# 1_Power.net
KiCad netlist of a schematic drawn in Altium Designer
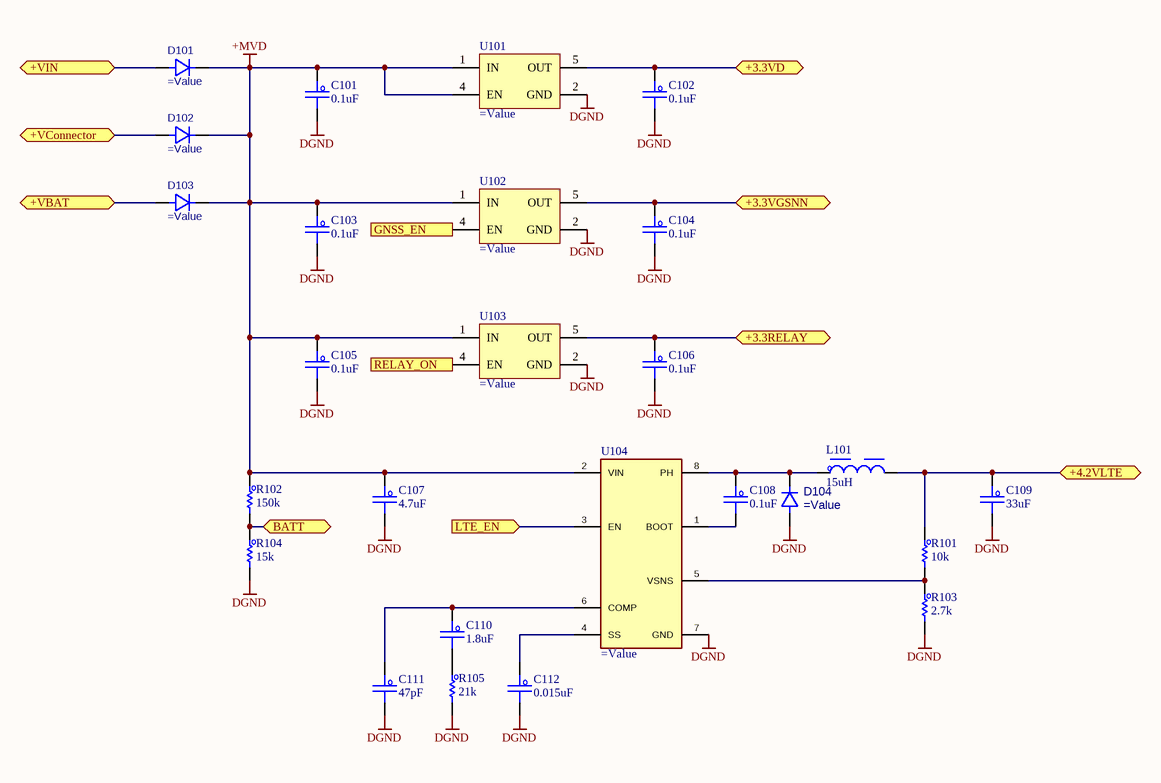
[diagram p0: 1_Power.SchDoc]

(export (version "E")
  (design (tool "Eeschema 10.0.6"))
  (components
    (comp (ref "C101")
      (value "0.1uF")
      (footprint "C_0603")
      (description "CAP CER 0.1UF 50V X7R 0603")
      (fields (field (name "MANUFACTURER") "KEMET") (field (name "PARTNUMBER") "C0603C104K5RACTU"))
      (libsource (lib "UUSymbol") (part "C_Capacitor"))
    )
    (comp (ref "C102")
      (value "0.1uF")
      (footprint "C_0603")
      (description "CAP CER 0.1UF 50V X7R 0603")
      (fields (field (name "MANUFACTURER") "KEMET") (field (name "PARTNUMBER") "C0603C104K5RACTU"))
      (libsource (lib "UUSymbol") (part "C_Capacitor"))
    )
    (comp (ref "C103")
      (value "0.1uF")
      (footprint "C_0603")
      (description "CAP CER 0.1UF 50V X7R 0603")
      (fields (field (name "MANUFACTURER") "KEMET") (field (name "PARTNUMBER") "C0603C104K5RACTU"))
      (libsource (lib "UUSymbol") (part "C_Capacitor"))
    )
    (comp (ref "C104")
      (value "0.1uF")
      (footprint "C_0603")
      (description "CAP CER 0.1UF 50V X7R 0603")
      (fields (field (name "MANUFACTURER") "KEMET") (field (name "PARTNUMBER") "C0603C104K5RACTU"))
      (libsource (lib "UUSymbol") (part "C_Capacitor"))
    )
    (comp (ref "C105")
      (value "0.1uF")
      (footprint "C_0603")
      (description "CAP CER 0.1UF 50V X7R 0603")
      (fields (field (name "MANUFACTURER") "KEMET") (field (name "PARTNUMBER") "C0603C104K5RACTU"))
      (libsource (lib "UUSymbol") (part "C_Capacitor"))
    )
    (comp (ref "C106")
      (value "0.1uF")
      (footprint "C_0603")
      (description "CAP CER 0.1UF 50V X7R 0603")
      (fields (field (name "MANUFACTURER") "KEMET") (field (name "PARTNUMBER") "C0603C104K5RACTU"))
      (libsource (lib "UUSymbol") (part "C_Capacitor"))
    )
    (comp (ref "C107")
      (value "4.7uF")
      (footprint "C_1206")
      (description "CAP CER 4.7UF 50V X7R 1206")
      (fields (field (name "MANUFACTURER") "KEMET") (field (name "PARTNUMBER") "C1206C475K5RAC7800"))
      (libsource (lib "UUSymbol") (part "C_Capacitor"))
    )
    (comp (ref "C108")
      (value "0.1uF")
      (footprint "C_0603")
      (description "CAP CER 0.1UF 50V X7R 0603")
      (fields (field (name "MANUFACTURER") "KEMET") (field (name "PARTNUMBER") "C0603C104K5RACTU"))
      (libsource (lib "UUSymbol") (part "C_Capacitor"))
    )
    (comp (ref "C109")
      (value "33uF")
      (footprint "C_0805")
      (description "CAP CER 33UF 10V X5R 0805")
      (fields
        (field (name "MANUFACTURER") "TDK Corporation")
        (field (name "PARTNUMBER") "C2012X5R1A336M125AC")
      )
      (libsource (lib "UUSymbol") (part "C_Capacitor"))
    )
    (comp (ref "C110")
      (value "1.8uF")
      (footprint "C_0603")
      (description "CAP CER 1800PF 50V X7R 0603")
      (fields (field (name "MANUFACTURER") "KEMET") (field (name "PARTNUMBER") "C0603C182K5RAC7867"))
      (libsource (lib "UUSymbol") (part "C_Capacitor"))
    )
    (comp (ref "C111")
      (value "47pF")
      (footprint "C_0603")
      (description "CAP CER 47PF 50V X7R 0603")
      (fields (field (name "MANUFACTURER") "KEMET") (field (name "PARTNUMBER") "C0603C470J5RAC7867"))
      (libsource (lib "UUSymbol") (part "C_Capacitor"))
    )
    (comp (ref "C112")
      (value "0.015uF")
      (footprint "C_0603")
      (description "CAP CER 15PF 50V C0G/NP0 0603")
      (fields (field (name "MANUFACTURER") "KEMET") (field (name "PARTNUMBER") "C0603C150J5GAC7867"))
      (libsource (lib "UUSymbol") (part "C_Capacitor"))
    )
    (comp (ref "D101")
      (value "~")
      (footprint "SOD323")
      (description "DIODE SCHOTTKY 40V 2A 0603")
      (fields (field (name "MANUFACTURER") "Slkor(SLKORMICRO Elec.)") (field (name "PARTNUMBER") "SD103AWS"))
      (libsource (lib "UUSymbol") (part "D_PW_SD103AWS"))
    )
    (comp (ref "D102")
      (value "~")
      (footprint "SOD323")
      (description "DIODE SCHOTTKY 40V 2A 0603")
      (fields (field (name "MANUFACTURER") "Slkor(SLKORMICRO Elec.)") (field (name "PARTNUMBER") "SD103AWS"))
      (libsource (lib "UUSymbol") (part "D_PW_SD103AWS"))
    )
    (comp (ref "D103")
      (value "~")
      (footprint "SOD323")
      (description "DIODE SCHOTTKY 40V 2A 0603")
      (fields (field (name "MANUFACTURER") "Slkor(SLKORMICRO Elec.)") (field (name "PARTNUMBER") "SD103AWS"))
      (libsource (lib "UUSymbol") (part "D_PW_SD103AWS"))
    )
    (comp (ref "D104")
      (value "~")
      (footprint "DFN119P160X30-2M")
      (description "DIODE SCHOTTKY 30V 2A 0603")
      (fields
        (field (name "MANUFACTURER") "Vishay General Semiconductor - Diodes Division")
        (field (name "PARTNUMBER") "VSKY20301608-G4-08")
      )
      (libsource (lib "UUSymbol") (part "D_PW_VSKY20301608"))
    )
    (comp (ref "L101")
      (value "15uH")
      (footprint "IND_04054150_WRE")
      (description "FIXED IND 15UH 2A 86 MOHM SMD")
      (fields (field (name "MANUFACTURER") "Würth Elektronik") (field (name "PARTNUMBER") "74404054150"))
      (libsource (lib "UUSymbol") (part "L_74404054150"))
    )
    (comp (ref "R101")
      (value "10k")
      (footprint "R_0603")
      (description "RES 10K OHM 5% 1/10W 0603")
      (fields (field (name "MANUFACTURER") "Vishay Dale") (field (name "PARTNUMBER") "CRCW060310K0JNEBC"))
      (libsource (lib "UUSymbol") (part "R_Resister"))
    )
    (comp (ref "R102")
      (value "150k")
      (footprint "R_0603")
      (description "RES SMD 150K OHM 1% 1/10W 0603")
      (fields (field (name "MANUFACTURER") "Vishay Dale") (field (name "PARTNUMBER") "CRCW0603150KFKEAC"))
      (libsource (lib "UUSymbol") (part "R_Resister"))
    )
    (comp (ref "R103")
      (value "2.7k")
      (footprint "R_0603")
      (description "RES 2.7K OHM 5% 1/10W 0603")
      (fields (field (name "MANUFACTURER") "Vishay Dale") (field (name "PARTNUMBER") "CRCW06032K70JNEAC"))
      (libsource (lib "UUSymbol") (part "R_Resister"))
    )
    (comp (ref "R104")
      (value "15k")
      (footprint "R_0603")
      (description "RES 15K OHM 5% 1/10W 0603")
      (fields (field (name "MANUFACTURER") "Vishay Dale") (field (name "PARTNUMBER") "CRCW060315K0JNEAC"))
      (libsource (lib "UUSymbol") (part "R_Resister"))
    )
    (comp (ref "R105")
      (value "21k")
      (footprint "R_0603")
      (description "RES SMD 150K OHM 1% 1/10W 0603")
      (libsource (lib "UUSymbol") (part "R_Resister"))
    )
    (comp (ref "U101")
      (value "~")
      (footprint "SOT95P280X145-5N")
      (description "200mA 360mV@(10mA) Fixed 3.3V~3.3V Positive 1 36V SOT-23-5 Linear Voltage Regulators (LDO) ROHS")
      (fields (field (name "PARTNUMBER") "RT9069-33GB") (field (name "MANUFACTURER") "Richtek Tech"))
      (libsource (lib "UUSymbol") (part "IC_LDO_RT9069-33GB"))
    )
    (comp (ref "U102")
      (value "~")
      (footprint "SOT95P280X145-5N")
      (description "200mA 360mV@(10mA) Fixed 3.3V~3.3V Positive 1 36V SOT-23-5 Linear Voltage Regulators (LDO) ROHS")
      (fields (field (name "PARTNUMBER") "RT9069-33GB") (field (name "MANUFACTURER") "Richtek Tech"))
      (libsource (lib "UUSymbol") (part "IC_LDO_RT9069-33GB"))
    )
    (comp (ref "U103")
      (value "~")
      (footprint "SOT95P280X145-5N")
      (description "200mA 360mV@(10mA) Fixed 3.3V~3.3V Positive 1 36V SOT-23-5 Linear Voltage Regulators (LDO) ROHS")
      (fields (field (name "PARTNUMBER") "RT9069-33GB") (field (name "MANUFACTURER") "Richtek Tech"))
      (libsource (lib "UUSymbol") (part "IC_LDO_RT9069-33GB"))
    )
    (comp (ref "U104")
      (value "~")
      (footprint "SO-8_STM")
      (description "IC REG BUCK ADJUSTABLE 2A 8SOIC")
      (fields (field (name "PARTNUMBER") "TPS54231DR") (field (name "MANUFACTURER") "Texas Instruments"))
      (libsource (lib "UUSymbol") (part "IC_PMS_TPS54231DR"))
    )
  )
  (nets
    (net (code "1") (name "+MVD") (class "Default")
      (node (ref "C101") (pin "1") (pinfunction "1_1") (pintype "passive"))
      (node (ref "C103") (pin "1") (pinfunction "1_1") (pintype "passive"))
      (node (ref "C105") (pin "1") (pinfunction "1_1") (pintype "passive"))
      (node (ref "C107") (pin "1") (pinfunction "1_1") (pintype "passive"))
      (node (ref "D101") (pin "1") (pinfunction "1_1") (pintype "passive"))
      (node (ref "D102") (pin "1") (pinfunction "1_1") (pintype "passive"))
      (node (ref "D103") (pin "1") (pinfunction "1_1") (pintype "passive"))
      (node (ref "R102") (pin "1") (pinfunction "1_1") (pintype "passive"))
      (node (ref "U101") (pin "1") (pinfunction "IN_1") (pintype "passive"))
      (node (ref "U101") (pin "4") (pinfunction "EN_4") (pintype "passive"))
      (node (ref "U102") (pin "1") (pinfunction "IN_1") (pintype "passive"))
      (node (ref "U103") (pin "1") (pinfunction "IN_1") (pintype "passive"))
      (node (ref "U104") (pin "2") (pinfunction "VIN_2") (pintype "passive"))
    )
    (net (code "2") (name "/+3.3RELAY") (class "Default")
      (node (ref "C106") (pin "1") (pinfunction "1_1") (pintype "passive"))
      (node (ref "U103") (pin "5") (pinfunction "OUT_5") (pintype "passive"))
    )
    (net (code "3") (name "/+3.3VD") (class "Default")
      (node (ref "C102") (pin "1") (pinfunction "1_1") (pintype "passive"))
      (node (ref "U101") (pin "5") (pinfunction "OUT_5") (pintype "passive"))
    )
    (net (code "4") (name "/+3.3VGSNN") (class "Default")
      (node (ref "C104") (pin "1") (pinfunction "1_1") (pintype "passive"))
      (node (ref "U102") (pin "5") (pinfunction "OUT_5") (pintype "passive"))
    )
    (net (code "5") (name "/+4.2VLTE") (class "Default")
      (node (ref "C109") (pin "1") (pinfunction "1_1") (pintype "passive"))
      (node (ref "L101") (pin "2") (pinfunction "2_2") (pintype "passive"))
      (node (ref "R101") (pin "1") (pinfunction "1_1") (pintype "passive"))
    )
    (net (code "6") (name "/+VBAT") (class "Default")
      (node (ref "D103") (pin "2") (pinfunction "2_2") (pintype "passive"))
    )
    (net (code "7") (name "/+VConnector") (class "Default")
      (node (ref "D102") (pin "2") (pinfunction "2_2") (pintype "passive"))
    )
    (net (code "8") (name "/+VIN") (class "Default")
      (node (ref "D101") (pin "2") (pinfunction "2_2") (pintype "passive"))
    )
    (net (code "9") (name "/BATT") (class "Default")
      (node (ref "R102") (pin "2") (pinfunction "2_2") (pintype "passive"))
      (node (ref "R104") (pin "1") (pinfunction "1_1") (pintype "passive"))
    )
    (net (code "10") (name "/GNSS_EN") (class "Default")
      (node (ref "U102") (pin "4") (pinfunction "EN_4") (pintype "passive"))
    )
    (net (code "11") (name "/LTE_EN") (class "Default")
      (node (ref "U104") (pin "3") (pinfunction "EN_3") (pintype "passive"))
    )
    (net (code "12") (name "/RELAY_ON") (class "Default")
      (node (ref "U103") (pin "4") (pinfunction "EN_4") (pintype "passive"))
    )
    (net (code "13") (name "DGND") (class "Default")
      (node (ref "C101") (pin "2") (pinfunction "2_2") (pintype "passive"))
      (node (ref "C102") (pin "2") (pinfunction "2_2") (pintype "passive"))
      (node (ref "C103") (pin "2") (pinfunction "2_2") (pintype "passive"))
      (node (ref "C104") (pin "2") (pinfunction "2_2") (pintype "passive"))
      (node (ref "C105") (pin "2") (pinfunction "2_2") (pintype "passive"))
      (node (ref "C106") (pin "2") (pinfunction "2_2") (pintype "passive"))
      (node (ref "C107") (pin "2") (pinfunction "2_2") (pintype "passive"))
      (node (ref "C109") (pin "2") (pinfunction "2_2") (pintype "passive"))
      (node (ref "C111") (pin "2") (pinfunction "2_2") (pintype "passive"))
      (node (ref "C112") (pin "2") (pinfunction "2_2") (pintype "passive"))
      (node (ref "D104") (pin "2") (pinfunction "2_2") (pintype "passive"))
      (node (ref "R103") (pin "2") (pinfunction "2_2") (pintype "passive"))
      (node (ref "R104") (pin "2") (pinfunction "2_2") (pintype "passive"))
      (node (ref "R105") (pin "2") (pinfunction "2_2") (pintype "passive"))
      (node (ref "U101") (pin "2") (pinfunction "GND_2") (pintype "passive"))
      (node (ref "U102") (pin "2") (pinfunction "GND_2") (pintype "passive"))
      (node (ref "U103") (pin "2") (pinfunction "GND_2") (pintype "passive"))
      (node (ref "U104") (pin "7") (pinfunction "GND_7") (pintype "passive"))
    )
    (net (code "14") (name "Net-(C110-Pad2)") (class "Default")
      (node (ref "C110") (pin "2") (pinfunction "2_2") (pintype "passive"))
      (node (ref "R105") (pin "1") (pinfunction "1_1") (pintype "passive"))
    )
    (net (code "15") (name "Net-(U104-BOOT)") (class "Default")
      (node (ref "C108") (pin "2") (pinfunction "2_2") (pintype "passive"))
      (node (ref "U104") (pin "1") (pinfunction "BOOT_1") (pintype "passive"))
    )
    (net (code "16") (name "Net-(U104-COMP)") (class "Default")
      (node (ref "C110") (pin "1") (pinfunction "1_1") (pintype "passive"))
      (node (ref "C111") (pin "1") (pinfunction "1_1") (pintype "passive"))
      (node (ref "U104") (pin "6") (pinfunction "COMP_6") (pintype "passive"))
    )
    (net (code "17") (name "Net-(U104-PH)") (class "Default")
      (node (ref "C108") (pin "1") (pinfunction "1_1") (pintype "passive"))
      (node (ref "D104") (pin "1") (pinfunction "1_1") (pintype "passive"))
      (node (ref "L101") (pin "1") (pinfunction "1_1") (pintype "passive"))
      (node (ref "U104") (pin "8") (pinfunction "PH_8") (pintype "passive"))
    )
    (net (code "18") (name "Net-(U104-SS)") (class "Default")
      (node (ref "C112") (pin "1") (pinfunction "1_1") (pintype "passive"))
      (node (ref "U104") (pin "4") (pinfunction "SS_4") (pintype "passive"))
    )
    (net (code "19") (name "Net-(U104-VSNS)") (class "Default")
      (node (ref "R101") (pin "2") (pinfunction "2_2") (pintype "passive"))
      (node (ref "R103") (pin "1") (pinfunction "1_1") (pintype "passive"))
      (node (ref "U104") (pin "5") (pinfunction "VSNS_5") (pintype "passive"))
    )
  )
)
